# Actuators.net
KiCad netlist of a schematic drawn in Altium Designer
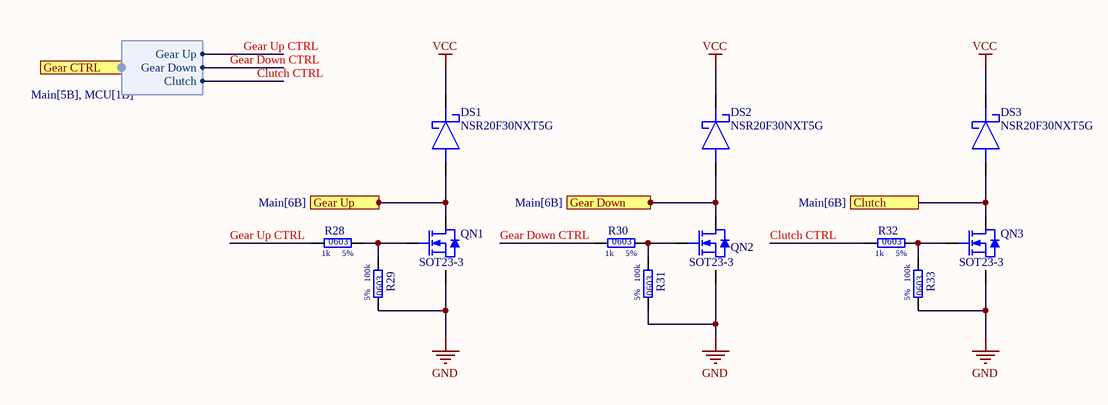
[diagram p0: Actuators.SchDoc]

(export (version "E")
  (design (tool "Eeschema 10.0.6"))
  (components
    (comp (ref "DS1")
      (value "DS_NSR20F30NXT5G")
      (footprint "0603")
      (description "Schottky, 480mV 2A 1.75W 0603")
      (fields (field (name "MAN. PART NUM.") "NSR20F30NXT5G") (field (name "POWER") "1.75W"))
      (libsource (lib "Altium Concord Pro on A365") (part "Diode Shottky"))
    )
    (comp (ref "DS2")
      (value "DS_NSR20F30NXT5G")
      (footprint "0603")
      (description "Schottky, 480mV 2A 1.75W 0603")
      (fields (field (name "MAN. PART NUM.") "NSR20F30NXT5G") (field (name "POWER") "1.75W"))
      (libsource (lib "Altium Concord Pro on A365") (part "Diode Shottky"))
    )
    (comp (ref "DS3")
      (value "DS_NSR20F30NXT5G")
      (footprint "0603")
      (description "Schottky, 480mV 2A 1.75W 0603")
      (fields (field (name "MAN. PART NUM.") "NSR20F30NXT5G") (field (name "POWER") "1.75W"))
      (libsource (lib "Altium Concord Pro on A365") (part "Diode Shottky"))
    )
    (comp (ref "QN1")
      (value "QN_IRLML6344TRPBF")
      (footprint "SOT23")
      (description "Trans MOSFET N-CH 30V 5A 3-Pin SOT-23 T/R")
      (fields (field (name "CASE/PACKAGE") "SOT23-3") (field (name "POWER") "1.3W"))
      (libsource (lib "Altium Concord Pro on A365") (part "NMOS"))
    )
    (comp (ref "QN2")
      (value "QN_IRLML6344TRPBF")
      (footprint "SOT23")
      (description "Trans MOSFET N-CH 30V 5A 3-Pin SOT-23 T/R")
      (fields (field (name "CASE/PACKAGE") "SOT23-3") (field (name "POWER") "1.3W"))
      (libsource (lib "Altium Concord Pro on A365") (part "NMOS"))
    )
    (comp (ref "QN3")
      (value "QN_IRLML6344TRPBF")
      (footprint "SOT23")
      (description "Trans MOSFET N-CH 30V 5A 3-Pin SOT-23 T/R")
      (fields (field (name "CASE/PACKAGE") "SOT23-3") (field (name "POWER") "1.3W"))
      (libsource (lib "Altium Concord Pro on A365") (part "NMOS"))
    )
    (comp (ref "R28")
      (value "R_1k_0603_5")
      (footprint "0603_HandSold_Resistor")
      (fields
        (field (name "TOLERANCE") "5%")
        (field (name "RESISTANCE") "1k")
        (field (name "CASE/PACKAGE") "0603")
        (field (name "POWER") "100mW")
      )
      (libsource (lib "Altium Concord Pro on A365") (part "Resistor"))
    )
    (comp (ref "R29")
      (value "R_100k_0603_5")
      (footprint "0603_HandSold_Resistor")
      (fields
        (field (name "TOLERANCE") "5%")
        (field (name "RESISTANCE") "100k")
        (field (name "CASE/PACKAGE") "0603")
        (field (name "POWER") "100mW")
      )
      (libsource (lib "Altium Concord Pro on A365") (part "Resistor"))
    )
    (comp (ref "R30")
      (value "R_1k_0603_5")
      (footprint "0603_HandSold_Resistor")
      (fields
        (field (name "TOLERANCE") "5%")
        (field (name "RESISTANCE") "1k")
        (field (name "CASE/PACKAGE") "0603")
        (field (name "POWER") "100mW")
      )
      (libsource (lib "Altium Concord Pro on A365") (part "Resistor"))
    )
    (comp (ref "R31")
      (value "R_100k_0603_5")
      (footprint "0603_HandSold_Resistor")
      (fields
        (field (name "TOLERANCE") "5%")
        (field (name "RESISTANCE") "100k")
        (field (name "CASE/PACKAGE") "0603")
        (field (name "POWER") "100mW")
      )
      (libsource (lib "Altium Concord Pro on A365") (part "Resistor"))
    )
    (comp (ref "R32")
      (value "R_1k_0603_5")
      (footprint "0603_HandSold_Resistor")
      (fields
        (field (name "TOLERANCE") "5%")
        (field (name "RESISTANCE") "1k")
        (field (name "CASE/PACKAGE") "0603")
        (field (name "POWER") "100mW")
      )
      (libsource (lib "Altium Concord Pro on A365") (part "Resistor"))
    )
    (comp (ref "R33")
      (value "R_100k_0603_5")
      (footprint "0603_HandSold_Resistor")
      (fields
        (field (name "TOLERANCE") "5%")
        (field (name "RESISTANCE") "100k")
        (field (name "CASE/PACKAGE") "0603")
        (field (name "POWER") "100mW")
      )
      (libsource (lib "Altium Concord Pro on A365") (part "Resistor"))
    )
  )
  (nets
    (net (code "2") (name "/Clutch") (class "Default")
      (node (ref "DS3") (pin "2") (pinfunction "A_2") (pintype "passive"))
      (node (ref "QN3") (pin "2") (pinfunction "D_2") (pintype "passive"))
    )
    (net (code "3") (name "/Clutch CTRL") (class "Default")
      (node (ref "R32") (pin "1") (pinfunction "1_1") (pintype "passive"))
    )
    (net (code "4") (name "/Gear Down") (class "Default")
      (node (ref "DS2") (pin "2") (pinfunction "A_2") (pintype "passive"))
      (node (ref "QN2") (pin "2") (pinfunction "D_2") (pintype "passive"))
    )
    (net (code "5") (name "/Gear Down CTRL") (class "Default")
      (node (ref "R30") (pin "1") (pinfunction "1_1") (pintype "passive"))
    )
    (net (code "6") (name "/Gear Up") (class "Default")
      (node (ref "DS1") (pin "2") (pinfunction "A_2") (pintype "passive"))
      (node (ref "QN1") (pin "2") (pinfunction "D_2") (pintype "passive"))
    )
    (net (code "7") (name "/Gear Up CTRL") (class "Default")
      (node (ref "R28") (pin "1") (pinfunction "1_1") (pintype "passive"))
    )
    (net (code "9") (name "GND") (class "Default")
      (node (ref "QN1") (pin "3") (pinfunction "S_3") (pintype "passive"))
      (node (ref "QN2") (pin "3") (pinfunction "S_3") (pintype "passive"))
      (node (ref "QN3") (pin "3") (pinfunction "S_3") (pintype "passive"))
      (node (ref "R29") (pin "2") (pinfunction "2_2") (pintype "passive"))
      (node (ref "R31") (pin "2") (pinfunction "2_2") (pintype "passive"))
      (node (ref "R33") (pin "2") (pinfunction "2_2") (pintype "passive"))
    )
    (net (code "10") (name "Net-(QN1-G)") (class "Default")
      (node (ref "QN1") (pin "1") (pinfunction "G_1") (pintype "passive"))
      (node (ref "R28") (pin "2") (pinfunction "2_2") (pintype "passive"))
      (node (ref "R29") (pin "1") (pinfunction "1_1") (pintype "passive"))
    )
    (net (code "11") (name "Net-(QN2-G)") (class "Default")
      (node (ref "QN2") (pin "1") (pinfunction "G_1") (pintype "passive"))
      (node (ref "R30") (pin "2") (pinfunction "2_2") (pintype "passive"))
      (node (ref "R31") (pin "1") (pinfunction "1_1") (pintype "passive"))
    )
    (net (code "12") (name "Net-(QN3-G)") (class "Default")
      (node (ref "QN3") (pin "1") (pinfunction "G_1") (pintype "passive"))
      (node (ref "R32") (pin "2") (pinfunction "2_2") (pintype "passive"))
      (node (ref "R33") (pin "1") (pinfunction "1_1") (pintype "passive"))
    )
    (net (code "13") (name "VCC") (class "Default")
      (node (ref "DS1") (pin "1") (pinfunction "K_1") (pintype "passive"))
      (node (ref "DS2") (pin "1") (pinfunction "K_1") (pintype "passive"))
      (node (ref "DS3") (pin "1") (pinfunction "K_1") (pintype "passive"))
    )
  )
)
